# AIM2_-_Bus_Interface_REVB.net
KiCad netlist of a schematic drawn in Altium Designer
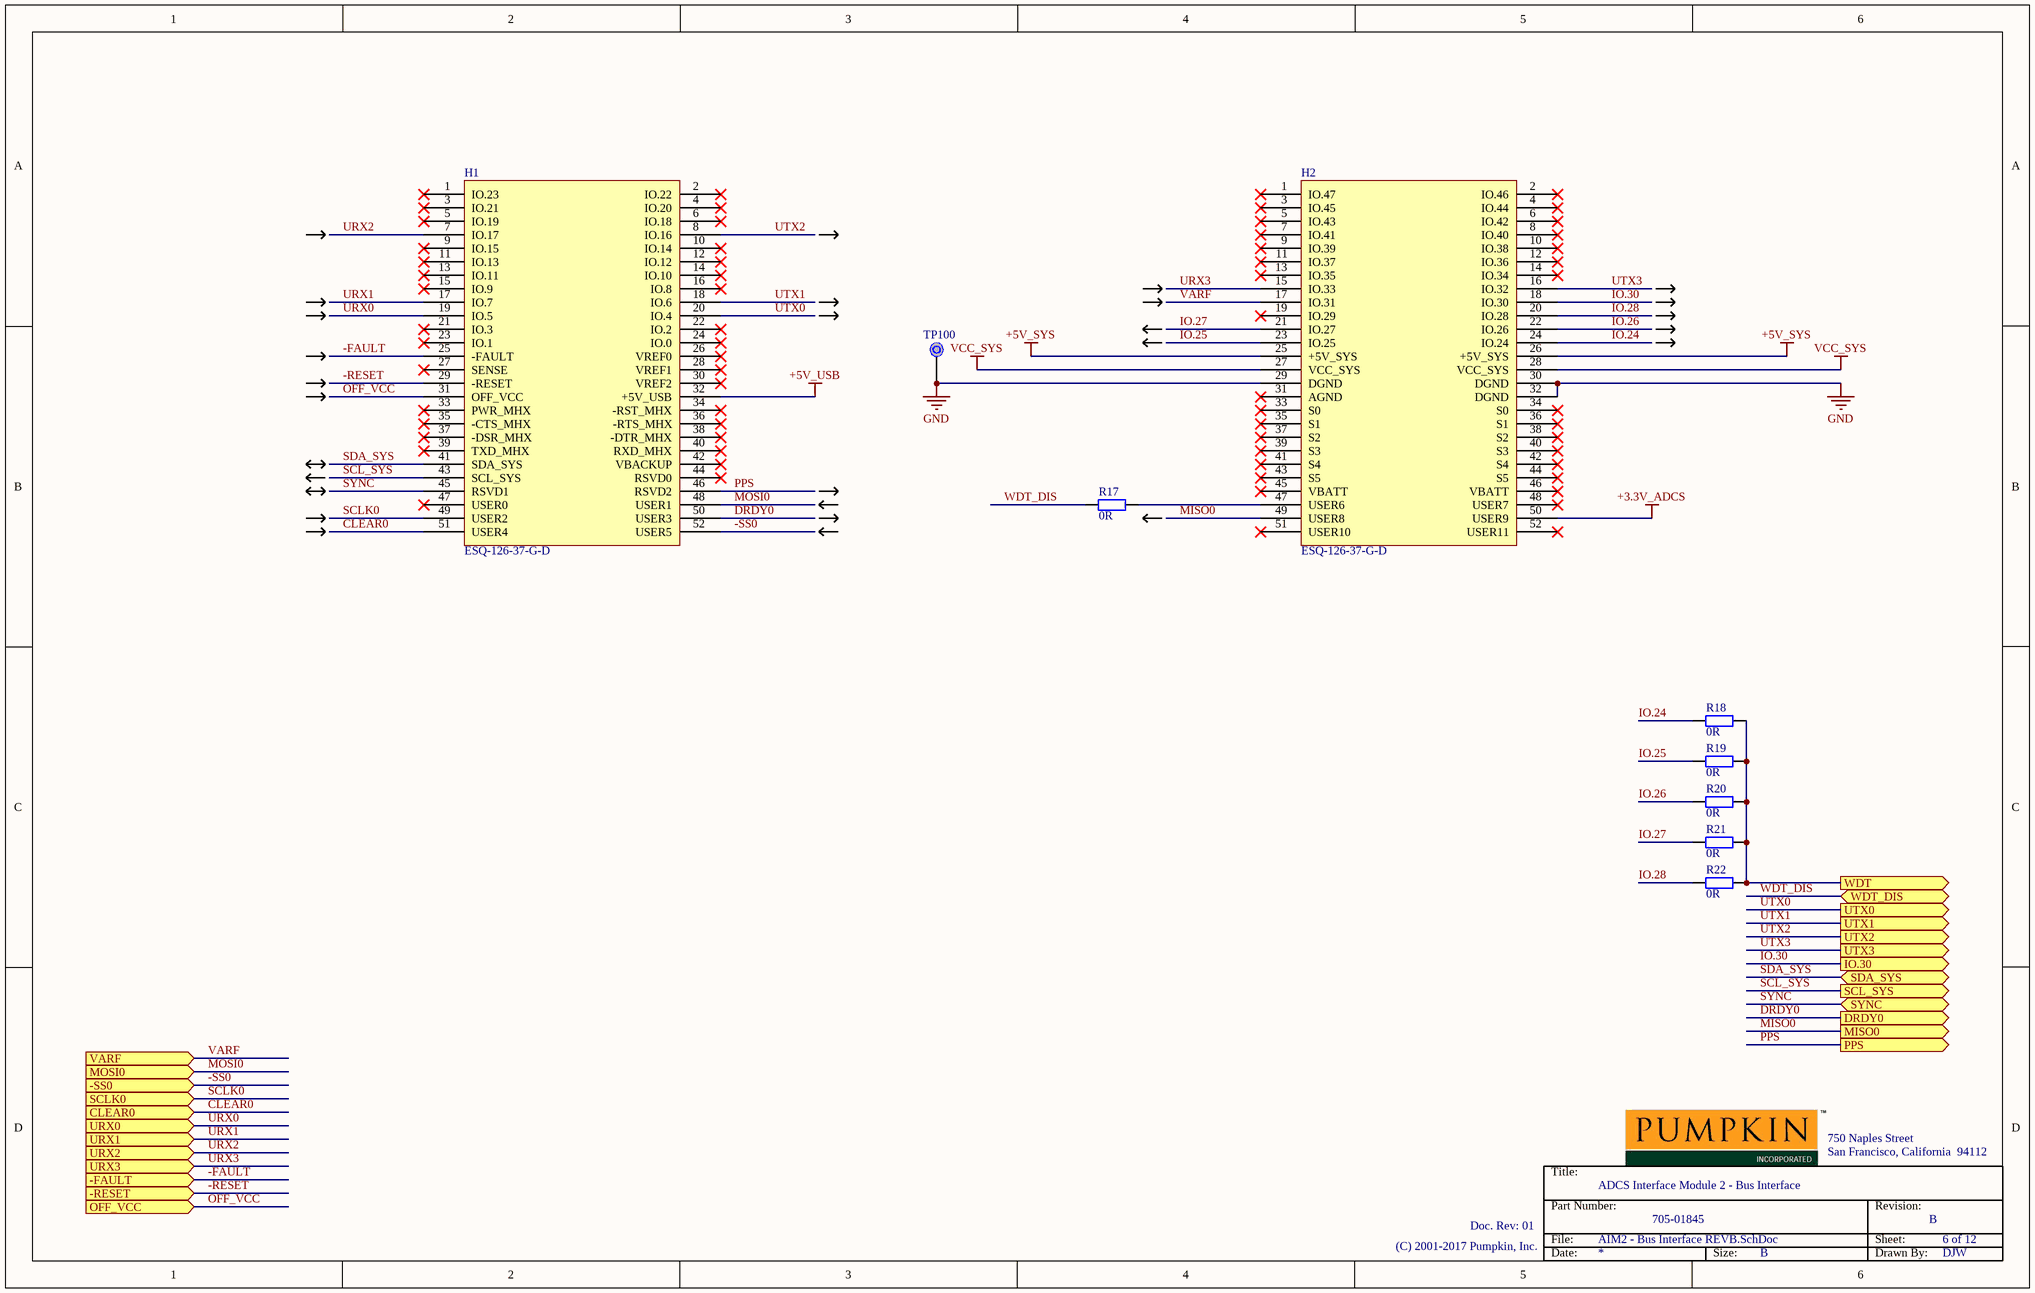
[diagram p0: AIM2 - Bus Interface REVB.SchDoc]

(export (version "E")
  (design (tool "Eeschema 10.0.6"))
  (components
    (comp (ref "H1")
      (value "ESQ-126-37-G-D")
      (footprint "ESQ-126-37-G-D")
      (description "Header PC/104 52-pin")
      (libsource (lib "Supernova Connectors") (part "CubesatBus-H1 ESQ-126-37-G-D"))
    )
    (comp (ref "H2")
      (value "ESQ-126-37-G-D")
      (footprint "ESQ-126-37-G-D")
      (description "Header PC/104 52-pin")
      (libsource (lib "Supernova Connectors") (part "CubesatBus-H2 ESQ-126-37-G-D"))
    )
    (comp (ref "R17")
      (value "0R")
      (footprint "0805 RES - DNP")
      (description "Resistor 0R 0805 0.125W")
      (libsource (lib "Supernova passives") (part "Resistor 0R 0805"))
    )
    (comp (ref "R18")
      (value "0R")
      (footprint "0805 RES - DNP")
      (description "Resistor 0R 0805 0.125W")
      (libsource (lib "Supernova passives") (part "Resistor 0R 0805"))
    )
    (comp (ref "R19")
      (value "0R")
      (footprint "0805 RES - DNP")
      (description "Resistor 0R 0805 0.125W")
      (libsource (lib "Supernova passives") (part "Resistor 0R 0805"))
    )
    (comp (ref "R20")
      (value "0R")
      (footprint "0805 RES - DNP")
      (description "Resistor 0R 0805 0.125W")
      (libsource (lib "Supernova passives") (part "Resistor 0R 0805"))
    )
    (comp (ref "R21")
      (value "0R")
      (footprint "0805 RES - DNP")
      (description "Resistor 0R 0805 0.125W")
      (libsource (lib "Supernova passives") (part "Resistor 0R 0805"))
    )
    (comp (ref "R22")
      (value "0R")
      (footprint "0805 RES - DNP")
      (description "Resistor 0R 0805 0.125W")
      (libsource (lib "Supernova passives") (part "Resistor 0R 0805"))
    )
    (comp (ref "TP100")
      (value "GND Testpoint")
      (footprint "GND Testpoint")
      (description "Testpoint GND")
      (libsource (lib "Supernova") (part "GND Testpoint"))
    )
  )
  (nets
    (net (code "1") (name "+3.3V_ADCS") (class "Default")
      (node (ref "H2") (pin "50") (pinfunction "USER9_50") (pintype "passive"))
    )
    (net (code "2") (name "+5V_SYS") (class "Default")
      (node (ref "H2") (pin "25") (pinfunction "+5V_SYS_25") (pintype "passive"))
      (node (ref "H2") (pin "26") (pinfunction "+5V_SYS_26") (pintype "passive"))
    )
    (net (code "3") (name "+5V_USB") (class "Default")
      (node (ref "H1") (pin "32") (pinfunction "+5V_USB_32") (pintype "passive"))
    )
    (net (code "4") (name "/-FAULT") (class "Default")
      (node (ref "H1") (pin "25") (pinfunction "-FAULT_25") (pintype "passive"))
    )
    (net (code "5") (name "/-RESET") (class "Default")
      (node (ref "H1") (pin "29") (pinfunction "-RESET_29") (pintype "passive"))
    )
    (net (code "6") (name "/-SS0") (class "Default")
      (node (ref "H1") (pin "52") (pinfunction "USER5_52") (pintype "passive"))
    )
    (net (code "7") (name "/CLEAR0") (class "Default")
      (node (ref "H1") (pin "51") (pinfunction "USER4_51") (pintype "passive"))
    )
    (net (code "8") (name "/DRDY0") (class "Default")
      (node (ref "H1") (pin "50") (pinfunction "USER3_50") (pintype "passive"))
    )
    (net (code "9") (name "/IO.24") (class "Default")
      (node (ref "H2") (pin "24") (pinfunction "IO.24_24") (pintype "passive"))
      (node (ref "R18") (pin "1") (pinfunction "1_1") (pintype "passive"))
    )
    (net (code "10") (name "/IO.25") (class "Default")
      (node (ref "H2") (pin "23") (pinfunction "IO.25_23") (pintype "passive"))
      (node (ref "R19") (pin "1") (pinfunction "1_1") (pintype "passive"))
    )
    (net (code "11") (name "/IO.26") (class "Default")
      (node (ref "H2") (pin "22") (pinfunction "IO.26_22") (pintype "passive"))
      (node (ref "R20") (pin "1") (pinfunction "1_1") (pintype "passive"))
    )
    (net (code "12") (name "/IO.27") (class "Default")
      (node (ref "H2") (pin "21") (pinfunction "IO.27_21") (pintype "passive"))
      (node (ref "R21") (pin "1") (pinfunction "1_1") (pintype "passive"))
    )
    (net (code "13") (name "/IO.28") (class "Default")
      (node (ref "H2") (pin "20") (pinfunction "IO.28_20") (pintype "passive"))
      (node (ref "R22") (pin "1") (pinfunction "1_1") (pintype "passive"))
    )
    (net (code "14") (name "/IO.30") (class "Default")
      (node (ref "H2") (pin "18") (pinfunction "IO.30_18") (pintype "passive"))
    )
    (net (code "15") (name "/MISO0") (class "Default")
      (node (ref "H2") (pin "49") (pinfunction "USER8_49") (pintype "passive"))
    )
    (net (code "16") (name "/MOSI0") (class "Default")
      (node (ref "H1") (pin "48") (pinfunction "USER1_48") (pintype "passive"))
    )
    (net (code "17") (name "/OFF_VCC") (class "Default")
      (node (ref "H1") (pin "31") (pinfunction "OFF_VCC_31") (pintype "passive"))
    )
    (net (code "18") (name "/PPS") (class "Default")
      (node (ref "H1") (pin "46") (pinfunction "RSVD2_46") (pintype "passive"))
    )
    (net (code "19") (name "/SCLK0") (class "Default")
      (node (ref "H1") (pin "49") (pinfunction "USER2_49") (pintype "passive"))
    )
    (net (code "20") (name "/SCL_SYS") (class "Default")
      (node (ref "H1") (pin "43") (pinfunction "SCL_SYS_43") (pintype "passive"))
    )
    (net (code "21") (name "/SDA_SYS") (class "Default")
      (node (ref "H1") (pin "41") (pinfunction "SDA_SYS_41") (pintype "passive"))
    )
    (net (code "22") (name "/SYNC") (class "Default")
      (node (ref "H1") (pin "45") (pinfunction "RSVD1_45") (pintype "passive"))
    )
    (net (code "23") (name "/URX0") (class "Default")
      (node (ref "H1") (pin "19") (pinfunction "IO.5_19") (pintype "passive"))
    )
    (net (code "24") (name "/URX1") (class "Default")
      (node (ref "H1") (pin "17") (pinfunction "IO.7_17") (pintype "passive"))
    )
    (net (code "25") (name "/URX2") (class "Default")
      (node (ref "H1") (pin "7") (pinfunction "IO.17_7") (pintype "passive"))
    )
    (net (code "26") (name "/URX3") (class "Default")
      (node (ref "H2") (pin "15") (pinfunction "IO.33_15") (pintype "passive"))
    )
    (net (code "27") (name "/UTX0") (class "Default")
      (node (ref "H1") (pin "20") (pinfunction "IO.4_20") (pintype "passive"))
    )
    (net (code "28") (name "/UTX1") (class "Default")
      (node (ref "H1") (pin "18") (pinfunction "IO.6_18") (pintype "passive"))
    )
    (net (code "29") (name "/UTX2") (class "Default")
      (node (ref "H1") (pin "8") (pinfunction "IO.16_8") (pintype "passive"))
    )
    (net (code "30") (name "/UTX3") (class "Default")
      (node (ref "H2") (pin "16") (pinfunction "IO.32_16") (pintype "passive"))
    )
    (net (code "31") (name "/VARF") (class "Default")
      (node (ref "H2") (pin "17") (pinfunction "IO.31_17") (pintype "passive"))
    )
    (net (code "32") (name "/WDT") (class "Default")
      (node (ref "R18") (pin "2") (pinfunction "2_2") (pintype "passive"))
      (node (ref "R19") (pin "2") (pinfunction "2_2") (pintype "passive"))
      (node (ref "R20") (pin "2") (pinfunction "2_2") (pintype "passive"))
      (node (ref "R21") (pin "2") (pinfunction "2_2") (pintype "passive"))
      (node (ref "R22") (pin "2") (pinfunction "2_2") (pintype "passive"))
    )
    (net (code "33") (name "/WDT_DIS") (class "Default")
      (node (ref "R17") (pin "1") (pinfunction "1_1") (pintype "passive"))
    )
    (net (code "34") (name "GND") (class "Default")
      (node (ref "H2") (pin "29") (pinfunction "DGND_29") (pintype "passive"))
      (node (ref "H2") (pin "30") (pinfunction "DGND_30") (pintype "passive"))
      (node (ref "H2") (pin "32") (pinfunction "DGND_32") (pintype "passive"))
      (node (ref "TP100") (pin "1") (pinfunction "1_1") (pintype "passive"))
    )
    (net (code "35") (name "Net-(H2-USER6)") (class "Default")
      (node (ref "H2") (pin "47") (pinfunction "USER6_47") (pintype "passive"))
      (node (ref "R17") (pin "2") (pinfunction "2_2") (pintype "passive"))
    )
    (net (code "36") (name "VCC_SYS") (class "Default")
      (node (ref "H2") (pin "27") (pinfunction "VCC_SYS_27") (pintype "passive"))
      (node (ref "H2") (pin "28") (pinfunction "VCC_SYS_28") (pintype "passive"))
    )
    (net (code "37") (name "unconnected-(H1--CTS_MHX-Pad35)") (class "Default")
      (node (ref "H1") (pin "35") (pinfunction "-CTS_MHX_35") (pintype "passive+no_connect"))
    )
    (net (code "38") (name "unconnected-(H1--DSR_MHX-Pad37)") (class "Default")
      (node (ref "H1") (pin "37") (pinfunction "-DSR_MHX_37") (pintype "passive+no_connect"))
    )
    (net (code "39") (name "unconnected-(H1--DTR_MHX-Pad38)") (class "Default")
      (node (ref "H1") (pin "38") (pinfunction "-DTR_MHX_38") (pintype "passive+no_connect"))
    )
    (net (code "40") (name "unconnected-(H1--RST_MHX-Pad34)") (class "Default")
      (node (ref "H1") (pin "34") (pinfunction "-RST_MHX_34") (pintype "passive+no_connect"))
    )
    (net (code "41") (name "unconnected-(H1--RTS_MHX-Pad36)") (class "Default")
      (node (ref "H1") (pin "36") (pinfunction "-RTS_MHX_36") (pintype "passive+no_connect"))
    )
    (net (code "42") (name "unconnected-(H1-IO.0-Pad24)") (class "Default")
      (node (ref "H1") (pin "24") (pinfunction "IO.0_24") (pintype "passive+no_connect"))
    )
    (net (code "43") (name "unconnected-(H1-IO.1-Pad23)") (class "Default")
      (node (ref "H1") (pin "23") (pinfunction "IO.1_23") (pintype "passive+no_connect"))
    )
    (net (code "44") (name "unconnected-(H1-IO.2-Pad22)") (class "Default")
      (node (ref "H1") (pin "22") (pinfunction "IO.2_22") (pintype "passive+no_connect"))
    )
    (net (code "45") (name "unconnected-(H1-IO.3-Pad21)") (class "Default")
      (node (ref "H1") (pin "21") (pinfunction "IO.3_21") (pintype "passive+no_connect"))
    )
    (net (code "46") (name "unconnected-(H1-IO.8-Pad16)") (class "Default")
      (node (ref "H1") (pin "16") (pinfunction "IO.8_16") (pintype "passive+no_connect"))
    )
    (net (code "47") (name "unconnected-(H1-IO.9-Pad15)") (class "Default")
      (node (ref "H1") (pin "15") (pinfunction "IO.9_15") (pintype "passive+no_connect"))
    )
    (net (code "48") (name "unconnected-(H1-IO.10-Pad14)") (class "Default")
      (node (ref "H1") (pin "14") (pinfunction "IO.10_14") (pintype "passive+no_connect"))
    )
    (net (code "49") (name "unconnected-(H1-IO.11-Pad13)") (class "Default")
      (node (ref "H1") (pin "13") (pinfunction "IO.11_13") (pintype "passive+no_connect"))
    )
    (net (code "50") (name "unconnected-(H1-IO.12-Pad12)") (class "Default")
      (node (ref "H1") (pin "12") (pinfunction "IO.12_12") (pintype "passive+no_connect"))
    )
    (net (code "51") (name "unconnected-(H1-IO.13-Pad11)") (class "Default")
      (node (ref "H1") (pin "11") (pinfunction "IO.13_11") (pintype "passive+no_connect"))
    )
    (net (code "52") (name "unconnected-(H1-IO.14-Pad10)") (class "Default")
      (node (ref "H1") (pin "10") (pinfunction "IO.14_10") (pintype "passive+no_connect"))
    )
    (net (code "53") (name "unconnected-(H1-IO.15-Pad9)") (class "Default")
      (node (ref "H1") (pin "9") (pinfunction "IO.15_9") (pintype "passive+no_connect"))
    )
    (net (code "54") (name "unconnected-(H1-IO.18-Pad6)") (class "Default")
      (node (ref "H1") (pin "6") (pinfunction "IO.18_6") (pintype "passive+no_connect"))
    )
    (net (code "55") (name "unconnected-(H1-IO.19-Pad5)") (class "Default")
      (node (ref "H1") (pin "5") (pinfunction "IO.19_5") (pintype "passive+no_connect"))
    )
    (net (code "56") (name "unconnected-(H1-IO.20-Pad4)") (class "Default")
      (node (ref "H1") (pin "4") (pinfunction "IO.20_4") (pintype "passive+no_connect"))
    )
    (net (code "57") (name "unconnected-(H1-IO.21-Pad3)") (class "Default")
      (node (ref "H1") (pin "3") (pinfunction "IO.21_3") (pintype "passive+no_connect"))
    )
    (net (code "58") (name "unconnected-(H1-IO.22-Pad2)") (class "Default")
      (node (ref "H1") (pin "2") (pinfunction "IO.22_2") (pintype "passive+no_connect"))
    )
    (net (code "59") (name "unconnected-(H1-IO.23-Pad1)") (class "Default")
      (node (ref "H1") (pin "1") (pinfunction "IO.23_1") (pintype "passive+no_connect"))
    )
    (net (code "60") (name "unconnected-(H1-PWR_MHX-Pad33)") (class "Default")
      (node (ref "H1") (pin "33") (pinfunction "PWR_MHX_33") (pintype "passive+no_connect"))
    )
    (net (code "61") (name "unconnected-(H1-RSVD0-Pad44)") (class "Default")
      (node (ref "H1") (pin "44") (pinfunction "RSVD0_44") (pintype "passive+no_connect"))
    )
    (net (code "62") (name "unconnected-(H1-RXD_MHX-Pad40)") (class "Default")
      (node (ref "H1") (pin "40") (pinfunction "RXD_MHX_40") (pintype "passive+no_connect"))
    )
    (net (code "63") (name "unconnected-(H1-SENSE-Pad27)") (class "Default")
      (node (ref "H1") (pin "27") (pinfunction "SENSE_27") (pintype "passive+no_connect"))
    )
    (net (code "64") (name "unconnected-(H1-TXD_MHX-Pad39)") (class "Default")
      (node (ref "H1") (pin "39") (pinfunction "TXD_MHX_39") (pintype "passive+no_connect"))
    )
    (net (code "65") (name "unconnected-(H1-USER0-Pad47)") (class "Default")
      (node (ref "H1") (pin "47") (pinfunction "USER0_47") (pintype "passive+no_connect"))
    )
    (net (code "66") (name "unconnected-(H1-VBACKUP-Pad42)") (class "Default")
      (node (ref "H1") (pin "42") (pinfunction "VBACKUP_42") (pintype "passive+no_connect"))
    )
    (net (code "67") (name "unconnected-(H1-VREF0-Pad26)") (class "Default")
      (node (ref "H1") (pin "26") (pinfunction "VREF0_26") (pintype "passive+no_connect"))
    )
    (net (code "68") (name "unconnected-(H1-VREF1-Pad28)") (class "Default")
      (node (ref "H1") (pin "28") (pinfunction "VREF1_28") (pintype "passive+no_connect"))
    )
    (net (code "69") (name "unconnected-(H1-VREF2-Pad30)") (class "Default")
      (node (ref "H1") (pin "30") (pinfunction "VREF2_30") (pintype "passive+no_connect"))
    )
    (net (code "70") (name "unconnected-(H2-AGND-Pad31)") (class "Default")
      (node (ref "H2") (pin "31") (pinfunction "AGND_31") (pintype "passive+no_connect"))
    )
    (net (code "71") (name "unconnected-(H2-IO.29-Pad19)") (class "Default")
      (node (ref "H2") (pin "19") (pinfunction "IO.29_19") (pintype "passive+no_connect"))
    )
    (net (code "72") (name "unconnected-(H2-IO.34-Pad14)") (class "Default")
      (node (ref "H2") (pin "14") (pinfunction "IO.34_14") (pintype "passive+no_connect"))
    )
    (net (code "73") (name "unconnected-(H2-IO.35-Pad13)") (class "Default")
      (node (ref "H2") (pin "13") (pinfunction "IO.35_13") (pintype "passive+no_connect"))
    )
    (net (code "74") (name "unconnected-(H2-IO.36-Pad12)") (class "Default")
      (node (ref "H2") (pin "12") (pinfunction "IO.36_12") (pintype "passive+no_connect"))
    )
    (net (code "75") (name "unconnected-(H2-IO.37-Pad11)") (class "Default")
      (node (ref "H2") (pin "11") (pinfunction "IO.37_11") (pintype "passive+no_connect"))
    )
    (net (code "76") (name "unconnected-(H2-IO.38-Pad10)") (class "Default")
      (node (ref "H2") (pin "10") (pinfunction "IO.38_10") (pintype "passive+no_connect"))
    )
    (net (code "77") (name "unconnected-(H2-IO.39-Pad9)") (class "Default")
      (node (ref "H2") (pin "9") (pinfunction "IO.39_9") (pintype "passive+no_connect"))
    )
    (net (code "78") (name "unconnected-(H2-IO.40-Pad8)") (class "Default")
      (node (ref "H2") (pin "8") (pinfunction "IO.40_8") (pintype "passive+no_connect"))
    )
    (net (code "79") (name "unconnected-(H2-IO.41-Pad7)") (class "Default")
      (node (ref "H2") (pin "7") (pinfunction "IO.41_7") (pintype "passive+no_connect"))
    )
    (net (code "80") (name "unconnected-(H2-IO.42-Pad6)") (class "Default")
      (node (ref "H2") (pin "6") (pinfunction "IO.42_6") (pintype "passive+no_connect"))
    )
    (net (code "81") (name "unconnected-(H2-IO.43-Pad5)") (class "Default")
      (node (ref "H2") (pin "5") (pinfunction "IO.43_5") (pintype "passive+no_connect"))
    )
    (net (code "82") (name "unconnected-(H2-IO.44-Pad4)") (class "Default")
      (node (ref "H2") (pin "4") (pinfunction "IO.44_4") (pintype "passive+no_connect"))
    )
    (net (code "83") (name "unconnected-(H2-IO.45-Pad3)") (class "Default")
      (node (ref "H2") (pin "3") (pinfunction "IO.45_3") (pintype "passive+no_connect"))
    )
    (net (code "84") (name "unconnected-(H2-IO.46-Pad2)") (class "Default")
      (node (ref "H2") (pin "2") (pinfunction "IO.46_2") (pintype "passive+no_connect"))
    )
    (net (code "85") (name "unconnected-(H2-IO.47-Pad1)") (class "Default")
      (node (ref "H2") (pin "1") (pinfunction "IO.47_1") (pintype "passive+no_connect"))
    )
    (net (code "86") (name "unconnected-(H2-S0-Pad33)") (class "Default")
      (node (ref "H2") (pin "33") (pinfunction "S0_33") (pintype "passive+no_connect"))
    )
    (net (code "87") (name "unconnected-(H2-S0-Pad34)") (class "Default")
      (node (ref "H2") (pin "34") (pinfunction "S0_34") (pintype "passive+no_connect"))
    )
    (net (code "88") (name "unconnected-(H2-S1-Pad35)") (class "Default")
      (node (ref "H2") (pin "35") (pinfunction "S1_35") (pintype "passive+no_connect"))
    )
    (net (code "89") (name "unconnected-(H2-S1-Pad36)") (class "Default")
      (node (ref "H2") (pin "36") (pinfunction "S1_36") (pintype "passive+no_connect"))
    )
    (net (code "90") (name "unconnected-(H2-S2-Pad37)") (class "Default")
      (node (ref "H2") (pin "37") (pinfunction "S2_37") (pintype "passive+no_connect"))
    )
    (net (code "91") (name "unconnected-(H2-S2-Pad38)") (class "Default")
      (node (ref "H2") (pin "38") (pinfunction "S2_38") (pintype "passive+no_connect"))
    )
    (net (code "92") (name "unconnected-(H2-S3-Pad39)") (class "Default")
      (node (ref "H2") (pin "39") (pinfunction "S3_39") (pintype "passive+no_connect"))
    )
    (net (code "93") (name "unconnected-(H2-S3-Pad40)") (class "Default")
      (node (ref "H2") (pin "40") (pinfunction "S3_40") (pintype "passive+no_connect"))
    )
    (net (code "94") (name "unconnected-(H2-S4-Pad41)") (class "Default")
      (node (ref "H2") (pin "41") (pinfunction "S4_41") (pintype "passive+no_connect"))
    )
    (net (code "95") (name "unconnected-(H2-S4-Pad42)") (class "Default")
      (node (ref "H2") (pin "42") (pinfunction "S4_42") (pintype "passive+no_connect"))
    )
    (net (code "96") (name "unconnected-(H2-S5-Pad43)") (class "Default")
      (node (ref "H2") (pin "43") (pinfunction "S5_43") (pintype "passive+no_connect"))
    )
    (net (code "97") (name "unconnected-(H2-S5-Pad44)") (class "Default")
      (node (ref "H2") (pin "44") (pinfunction "S5_44") (pintype "passive+no_connect"))
    )
    (net (code "98") (name "unconnected-(H2-USER7-Pad48)") (class "Default")
      (node (ref "H2") (pin "48") (pinfunction "USER7_48") (pintype "passive+no_connect"))
    )
    (net (code "99") (name "unconnected-(H2-USER10-Pad51)") (class "Default")
      (node (ref "H2") (pin "51") (pinfunction "USER10_51") (pintype "passive+no_connect"))
    )
    (net (code "100") (name "unconnected-(H2-USER11-Pad52)") (class "Default")
      (node (ref "H2") (pin "52") (pinfunction "USER11_52") (pintype "passive+no_connect"))
    )
    (net (code "101") (name "unconnected-(H2-VBATT-Pad45)") (class "Default")
      (node (ref "H2") (pin "45") (pinfunction "VBATT_45") (pintype "passive+no_connect"))
    )
    (net (code "102") (name "unconnected-(H2-VBATT-Pad46)") (class "Default")
      (node (ref "H2") (pin "46") (pinfunction "VBATT_46") (pintype "passive+no_connect"))
    )
  )
)
